# DIO.net
KiCad netlist of a schematic drawn in Altium Designer
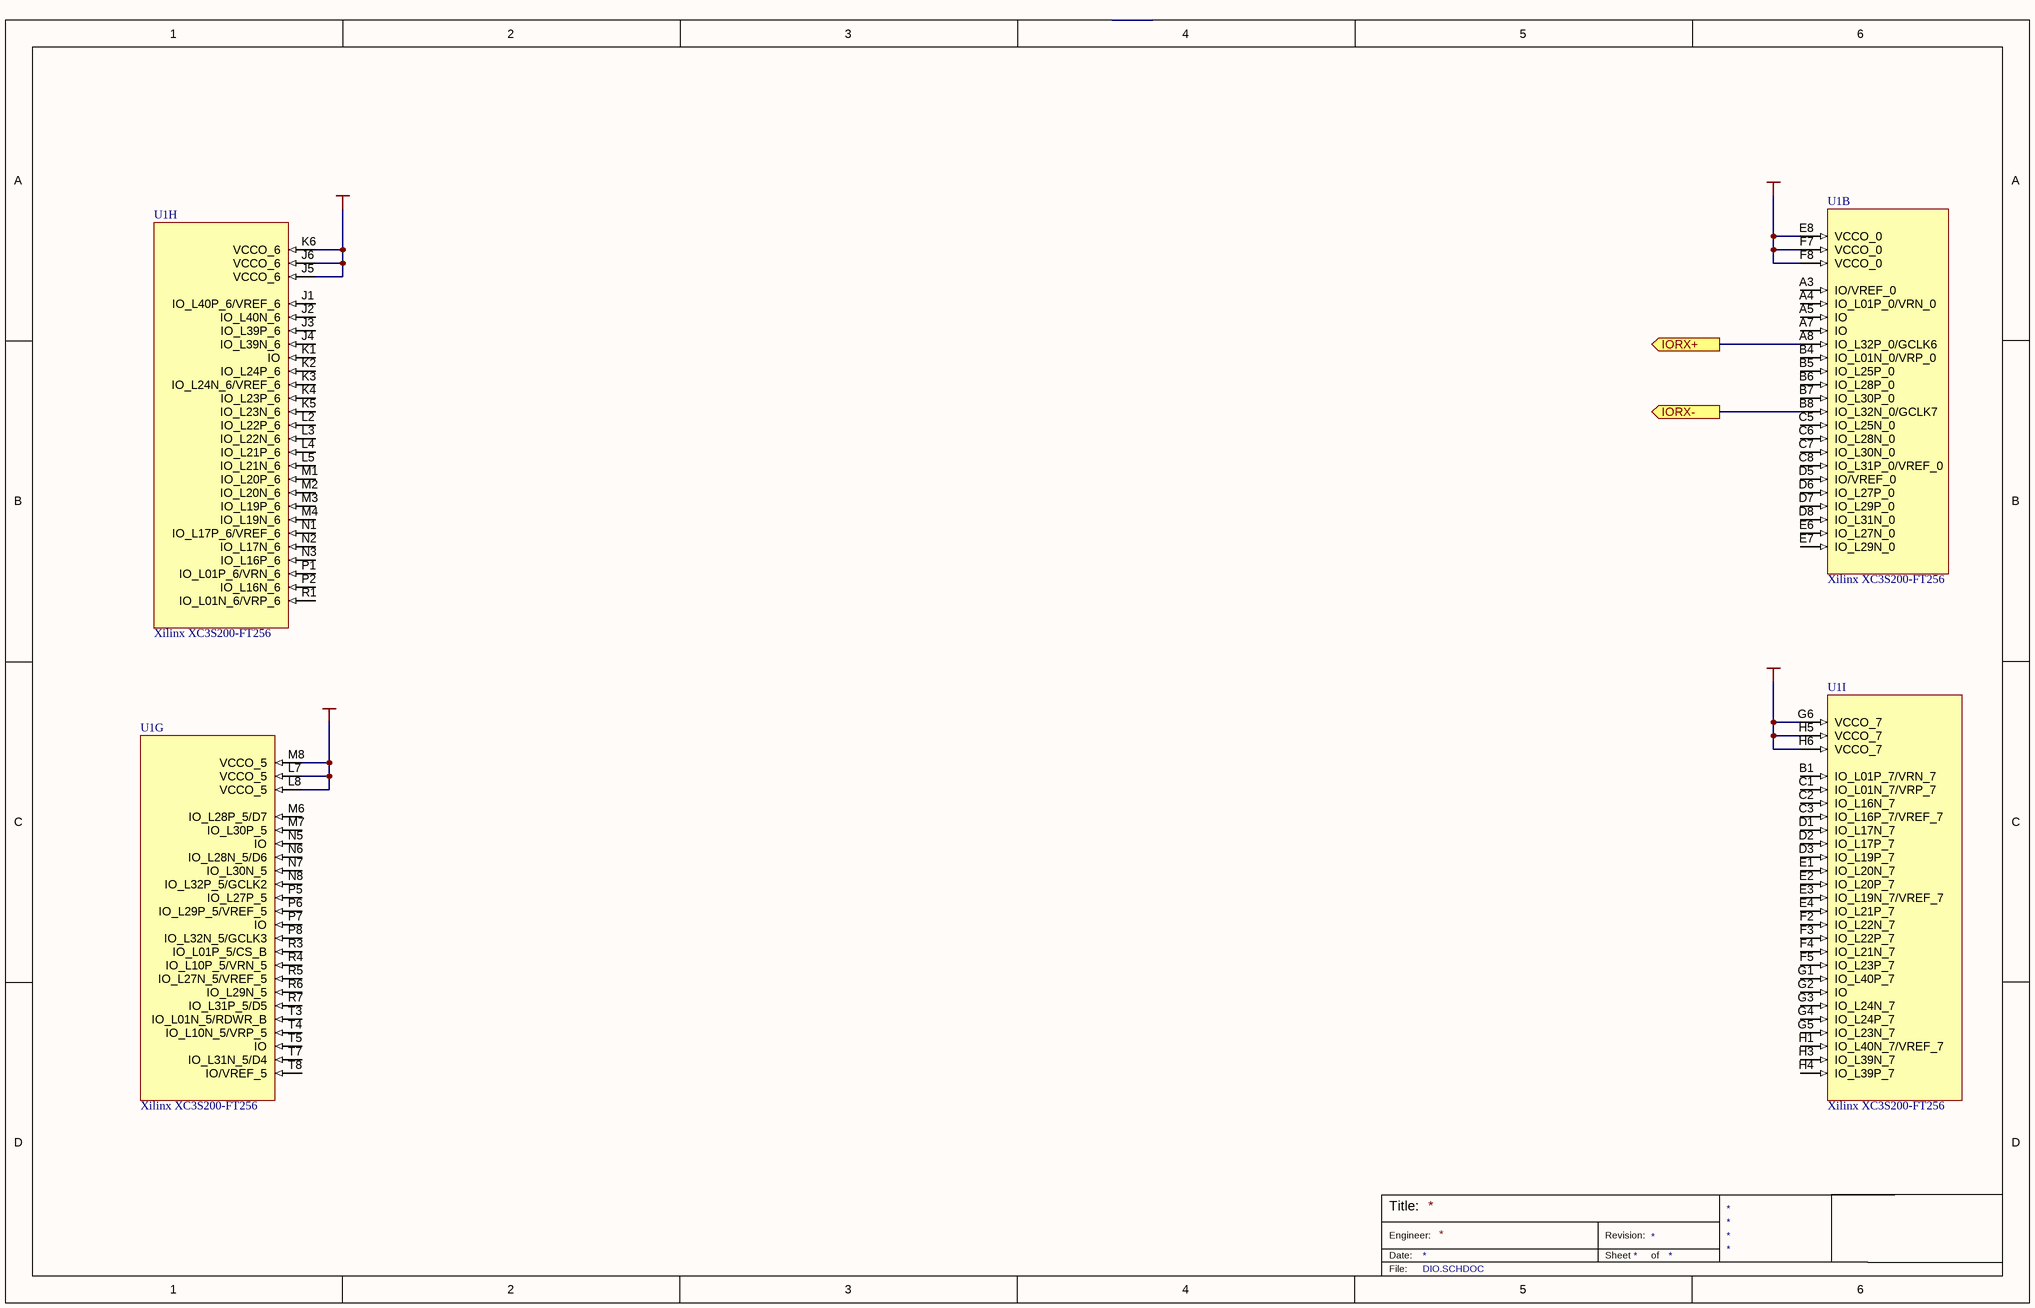
[diagram p0: DIO.SCHDOC]

(export (version "E")
  (design (tool "Eeschema 10.0.6"))
  (components
    (comp (ref "U1")
      (value "Xilinx XC3S200-FT256")
      (footprint "Xilinx FT256 BGA")
      (description "Xilinx Spartan-3 FPGA")
      (libsource (lib "") (part "XC3S200-FT256_1"))
    )
  )
  (nets
    (net (code "1") (name "+2.5VCC") (class "Default")
      (node (ref "U1") (pin "E8") (pinfunction "VCCO_0_E8") (pintype "input"))
      (node (ref "U1") (pin "F7") (pinfunction "VCCO_0_F7") (pintype "input"))
      (node (ref "U1") (pin "F8") (pinfunction "VCCO_0_F8") (pintype "input"))
      (node (ref "U1") (pin "G6") (pinfunction "VCCO_7_G6") (pintype "input"))
      (node (ref "U1") (pin "H5") (pinfunction "VCCO_7_H5") (pintype "input"))
      (node (ref "U1") (pin "H6") (pinfunction "VCCO_7_H6") (pintype "input"))
      (node (ref "U1") (pin "J5") (pinfunction "VCCO_6_J5") (pintype "input"))
      (node (ref "U1") (pin "J6") (pinfunction "VCCO_6_J6") (pintype "input"))
      (node (ref "U1") (pin "K6") (pinfunction "VCCO_6_K6") (pintype "input"))
      (node (ref "U1") (pin "L7") (pinfunction "VCCO_5_L7") (pintype "input"))
      (node (ref "U1") (pin "L8") (pinfunction "VCCO_5_L8") (pintype "input"))
      (node (ref "U1") (pin "M8") (pinfunction "VCCO_5_M8") (pintype "input"))
    )
    (net (code "2") (name "/IORX+") (class "Default")
      (node (ref "U1") (pin "A8") (pinfunction "IO_L32P_0/GCLK6_A8") (pintype "input"))
    )
    (net (code "3") (name "/IORX-") (class "Default")
      (node (ref "U1") (pin "B8") (pinfunction "IO_L32N_0/GCLK7_B8") (pintype "input"))
    )
    (net (code "4") (name "unconnected-(U1B-IO-PadA5)") (class "Default")
      (node (ref "U1") (pin "A5") (pinfunction "IO_A5") (pintype "input"))
    )
    (net (code "5") (name "unconnected-(U1B-IO-PadA7)") (class "Default")
      (node (ref "U1") (pin "A7") (pinfunction "IO_A7") (pintype "input"))
    )
    (net (code "6") (name "unconnected-(U1B-IO_L01N_0{slash}VRP_0-PadB4)") (class "Default")
      (node (ref "U1") (pin "B4") (pinfunction "IO_L01N_0/VRP_0_B4") (pintype "input"))
    )
    (net (code "7") (name "unconnected-(U1B-IO_L01P_0{slash}VRN_0-PadA4)") (class "Default")
      (node (ref "U1") (pin "A4") (pinfunction "IO_L01P_0/VRN_0_A4") (pintype "input"))
    )
    (net (code "8") (name "unconnected-(U1B-IO_L25N_0-PadC5)") (class "Default")
      (node (ref "U1") (pin "C5") (pinfunction "IO_L25N_0_C5") (pintype "input"))
    )
    (net (code "9") (name "unconnected-(U1B-IO_L25P_0-PadB5)") (class "Default")
      (node (ref "U1") (pin "B5") (pinfunction "IO_L25P_0_B5") (pintype "input"))
    )
    (net (code "10") (name "unconnected-(U1B-IO_L27N_0-PadE6)") (class "Default")
      (node (ref "U1") (pin "E6") (pinfunction "IO_L27N_0_E6") (pintype "input"))
    )
    (net (code "11") (name "unconnected-(U1B-IO_L27P_0-PadD6)") (class "Default")
      (node (ref "U1") (pin "D6") (pinfunction "IO_L27P_0_D6") (pintype "input"))
    )
    (net (code "12") (name "unconnected-(U1B-IO_L28N_0-PadC6)") (class "Default")
      (node (ref "U1") (pin "C6") (pinfunction "IO_L28N_0_C6") (pintype "input"))
    )
    (net (code "13") (name "unconnected-(U1B-IO_L28P_0-PadB6)") (class "Default")
      (node (ref "U1") (pin "B6") (pinfunction "IO_L28P_0_B6") (pintype "input"))
    )
    (net (code "14") (name "unconnected-(U1B-IO_L29N_0-PadE7)") (class "Default")
      (node (ref "U1") (pin "E7") (pinfunction "IO_L29N_0_E7") (pintype "input"))
    )
    (net (code "15") (name "unconnected-(U1B-IO_L29P_0-PadD7)") (class "Default")
      (node (ref "U1") (pin "D7") (pinfunction "IO_L29P_0_D7") (pintype "input"))
    )
    (net (code "16") (name "unconnected-(U1B-IO_L30N_0-PadC7)") (class "Default")
      (node (ref "U1") (pin "C7") (pinfunction "IO_L30N_0_C7") (pintype "input"))
    )
    (net (code "17") (name "unconnected-(U1B-IO_L30P_0-PadB7)") (class "Default")
      (node (ref "U1") (pin "B7") (pinfunction "IO_L30P_0_B7") (pintype "input"))
    )
    (net (code "18") (name "unconnected-(U1B-IO_L31N_0-PadD8)") (class "Default")
      (node (ref "U1") (pin "D8") (pinfunction "IO_L31N_0_D8") (pintype "input"))
    )
    (net (code "19") (name "unconnected-(U1B-IO_L31P_0{slash}VREF_0-PadC8)") (class "Default")
      (node (ref "U1") (pin "C8") (pinfunction "IO_L31P_0/VREF_0_C8") (pintype "input"))
    )
    (net (code "20") (name "unconnected-(U1B-IO{slash}VREF_0-PadA3)") (class "Default")
      (node (ref "U1") (pin "A3") (pinfunction "IO/VREF_0_A3") (pintype "input"))
    )
    (net (code "21") (name "unconnected-(U1B-IO{slash}VREF_0-PadD5)") (class "Default")
      (node (ref "U1") (pin "D5") (pinfunction "IO/VREF_0_D5") (pintype "input"))
    )
    (net (code "22") (name "unconnected-(U1G-IO-PadN5)") (class "Default")
      (node (ref "U1") (pin "N5") (pinfunction "IO_N5") (pintype "input"))
    )
    (net (code "23") (name "unconnected-(U1G-IO-PadP7)") (class "Default")
      (node (ref "U1") (pin "P7") (pinfunction "IO_P7") (pintype "input"))
    )
    (net (code "24") (name "unconnected-(U1G-IO-PadT5)") (class "Default")
      (node (ref "U1") (pin "T5") (pinfunction "IO_T5") (pintype "input"))
    )
    (net (code "25") (name "unconnected-(U1G-IO_L01N_5{slash}RDWR_B-PadT3)") (class "Default")
      (node (ref "U1") (pin "T3") (pinfunction "IO_L01N_5/RDWR_B_T3") (pintype "input"))
    )
    (net (code "26") (name "unconnected-(U1G-IO_L01P_5{slash}CS_B-PadR3)") (class "Default")
      (node (ref "U1") (pin "R3") (pinfunction "IO_L01P_5/CS_B_R3") (pintype "input"))
    )
    (net (code "27") (name "unconnected-(U1G-IO_L10N_5{slash}VRP_5-PadT4)") (class "Default")
      (node (ref "U1") (pin "T4") (pinfunction "IO_L10N_5/VRP_5_T4") (pintype "input"))
    )
    (net (code "28") (name "unconnected-(U1G-IO_L10P_5{slash}VRN_5-PadR4)") (class "Default")
      (node (ref "U1") (pin "R4") (pinfunction "IO_L10P_5/VRN_5_R4") (pintype "input"))
    )
    (net (code "29") (name "unconnected-(U1G-IO_L27N_5{slash}VREF_5-PadR5)") (class "Default")
      (node (ref "U1") (pin "R5") (pinfunction "IO_L27N_5/VREF_5_R5") (pintype "input"))
    )
    (net (code "30") (name "unconnected-(U1G-IO_L27P_5-PadP5)") (class "Default")
      (node (ref "U1") (pin "P5") (pinfunction "IO_L27P_5_P5") (pintype "input"))
    )
    (net (code "31") (name "unconnected-(U1G-IO_L28N_5{slash}D6-PadN6)") (class "Default")
      (node (ref "U1") (pin "N6") (pinfunction "IO_L28N_5/D6_N6") (pintype "input"))
    )
    (net (code "32") (name "unconnected-(U1G-IO_L28P_5{slash}D7-PadM6)") (class "Default")
      (node (ref "U1") (pin "M6") (pinfunction "IO_L28P_5/D7_M6") (pintype "input"))
    )
    (net (code "33") (name "unconnected-(U1G-IO_L29N_5-PadR6)") (class "Default")
      (node (ref "U1") (pin "R6") (pinfunction "IO_L29N_5_R6") (pintype "input"))
    )
    (net (code "34") (name "unconnected-(U1G-IO_L29P_5{slash}VREF_5-PadP6)") (class "Default")
      (node (ref "U1") (pin "P6") (pinfunction "IO_L29P_5/VREF_5_P6") (pintype "input"))
    )
    (net (code "35") (name "unconnected-(U1G-IO_L30N_5-PadN7)") (class "Default")
      (node (ref "U1") (pin "N7") (pinfunction "IO_L30N_5_N7") (pintype "input"))
    )
    (net (code "36") (name "unconnected-(U1G-IO_L30P_5-PadM7)") (class "Default")
      (node (ref "U1") (pin "M7") (pinfunction "IO_L30P_5_M7") (pintype "input"))
    )
    (net (code "37") (name "unconnected-(U1G-IO_L31N_5{slash}D4-PadT7)") (class "Default")
      (node (ref "U1") (pin "T7") (pinfunction "IO_L31N_5/D4_T7") (pintype "input"))
    )
    (net (code "38") (name "unconnected-(U1G-IO_L31P_5{slash}D5-PadR7)") (class "Default")
      (node (ref "U1") (pin "R7") (pinfunction "IO_L31P_5/D5_R7") (pintype "input"))
    )
    (net (code "39") (name "unconnected-(U1G-IO_L32N_5{slash}GCLK3-PadP8)") (class "Default")
      (node (ref "U1") (pin "P8") (pinfunction "IO_L32N_5/GCLK3_P8") (pintype "input"))
    )
    (net (code "40") (name "unconnected-(U1G-IO_L32P_5{slash}GCLK2-PadN8)") (class "Default")
      (node (ref "U1") (pin "N8") (pinfunction "IO_L32P_5/GCLK2_N8") (pintype "input"))
    )
    (net (code "41") (name "unconnected-(U1G-IO{slash}VREF_5-PadT8)") (class "Default")
      (node (ref "U1") (pin "T8") (pinfunction "IO/VREF_5_T8") (pintype "input"))
    )
    (net (code "42") (name "unconnected-(U1H-IO-PadK1)") (class "Default")
      (node (ref "U1") (pin "K1") (pinfunction "IO_K1") (pintype "input"))
    )
    (net (code "43") (name "unconnected-(U1H-IO_L01N_6{slash}VRP_6-PadR1)") (class "Default")
      (node (ref "U1") (pin "R1") (pinfunction "IO_L01N_6/VRP_6_R1") (pintype "input"))
    )
    (net (code "44") (name "unconnected-(U1H-IO_L01P_6{slash}VRN_6-PadP1)") (class "Default")
      (node (ref "U1") (pin "P1") (pinfunction "IO_L01P_6/VRN_6_P1") (pintype "input"))
    )
    (net (code "45") (name "unconnected-(U1H-IO_L16N_6-PadP2)") (class "Default")
      (node (ref "U1") (pin "P2") (pinfunction "IO_L16N_6_P2") (pintype "input"))
    )
    (net (code "46") (name "unconnected-(U1H-IO_L16P_6-PadN3)") (class "Default")
      (node (ref "U1") (pin "N3") (pinfunction "IO_L16P_6_N3") (pintype "input"))
    )
    (net (code "47") (name "unconnected-(U1H-IO_L17N_6-PadN2)") (class "Default")
      (node (ref "U1") (pin "N2") (pinfunction "IO_L17N_6_N2") (pintype "input"))
    )
    (net (code "48") (name "unconnected-(U1H-IO_L17P_6{slash}VREF_6-PadN1)") (class "Default")
      (node (ref "U1") (pin "N1") (pinfunction "IO_L17P_6/VREF_6_N1") (pintype "input"))
    )
    (net (code "49") (name "unconnected-(U1H-IO_L19N_6-PadM4)") (class "Default")
      (node (ref "U1") (pin "M4") (pinfunction "IO_L19N_6_M4") (pintype "input"))
    )
    (net (code "50") (name "unconnected-(U1H-IO_L19P_6-PadM3)") (class "Default")
      (node (ref "U1") (pin "M3") (pinfunction "IO_L19P_6_M3") (pintype "input"))
    )
    (net (code "51") (name "unconnected-(U1H-IO_L20N_6-PadM2)") (class "Default")
      (node (ref "U1") (pin "M2") (pinfunction "IO_L20N_6_M2") (pintype "input"))
    )
    (net (code "52") (name "unconnected-(U1H-IO_L20P_6-PadM1)") (class "Default")
      (node (ref "U1") (pin "M1") (pinfunction "IO_L20P_6_M1") (pintype "input"))
    )
    (net (code "53") (name "unconnected-(U1H-IO_L21N_6-PadL5)") (class "Default")
      (node (ref "U1") (pin "L5") (pinfunction "IO_L21N_6_L5") (pintype "input"))
    )
    (net (code "54") (name "unconnected-(U1H-IO_L21P_6-PadL4)") (class "Default")
      (node (ref "U1") (pin "L4") (pinfunction "IO_L21P_6_L4") (pintype "input"))
    )
    (net (code "55") (name "unconnected-(U1H-IO_L22N_6-PadL3)") (class "Default")
      (node (ref "U1") (pin "L3") (pinfunction "IO_L22N_6_L3") (pintype "input"))
    )
    (net (code "56") (name "unconnected-(U1H-IO_L22P_6-PadL2)") (class "Default")
      (node (ref "U1") (pin "L2") (pinfunction "IO_L22P_6_L2") (pintype "input"))
    )
    (net (code "57") (name "unconnected-(U1H-IO_L23N_6-PadK5)") (class "Default")
      (node (ref "U1") (pin "K5") (pinfunction "IO_L23N_6_K5") (pintype "input"))
    )
    (net (code "58") (name "unconnected-(U1H-IO_L23P_6-PadK4)") (class "Default")
      (node (ref "U1") (pin "K4") (pinfunction "IO_L23P_6_K4") (pintype "input"))
    )
    (net (code "59") (name "unconnected-(U1H-IO_L24N_6{slash}VREF_6-PadK3)") (class "Default")
      (node (ref "U1") (pin "K3") (pinfunction "IO_L24N_6/VREF_6_K3") (pintype "input"))
    )
    (net (code "60") (name "unconnected-(U1H-IO_L24P_6-PadK2)") (class "Default")
      (node (ref "U1") (pin "K2") (pinfunction "IO_L24P_6_K2") (pintype "input"))
    )
    (net (code "61") (name "unconnected-(U1H-IO_L39N_6-PadJ4)") (class "Default")
      (node (ref "U1") (pin "J4") (pinfunction "IO_L39N_6_J4") (pintype "input"))
    )
    (net (code "62") (name "unconnected-(U1H-IO_L39P_6-PadJ3)") (class "Default")
      (node (ref "U1") (pin "J3") (pinfunction "IO_L39P_6_J3") (pintype "input"))
    )
    (net (code "63") (name "unconnected-(U1H-IO_L40N_6-PadJ2)") (class "Default")
      (node (ref "U1") (pin "J2") (pinfunction "IO_L40N_6_J2") (pintype "input"))
    )
    (net (code "64") (name "unconnected-(U1H-IO_L40P_6{slash}VREF_6-PadJ1)") (class "Default")
      (node (ref "U1") (pin "J1") (pinfunction "IO_L40P_6/VREF_6_J1") (pintype "input"))
    )
    (net (code "65") (name "unconnected-(U1I-IO-PadG2)") (class "Default")
      (node (ref "U1") (pin "G2") (pinfunction "IO_G2") (pintype "input"))
    )
    (net (code "66") (name "unconnected-(U1I-IO_L01N_7{slash}VRP_7-PadC1)") (class "Default")
      (node (ref "U1") (pin "C1") (pinfunction "IO_L01N_7/VRP_7_C1") (pintype "input"))
    )
    (net (code "67") (name "unconnected-(U1I-IO_L01P_7{slash}VRN_7-PadB1)") (class "Default")
      (node (ref "U1") (pin "B1") (pinfunction "IO_L01P_7/VRN_7_B1") (pintype "input"))
    )
    (net (code "68") (name "unconnected-(U1I-IO_L16N_7-PadC2)") (class "Default")
      (node (ref "U1") (pin "C2") (pinfunction "IO_L16N_7_C2") (pintype "input"))
    )
    (net (code "69") (name "unconnected-(U1I-IO_L16P_7{slash}VREF_7-PadC3)") (class "Default")
      (node (ref "U1") (pin "C3") (pinfunction "IO_L16P_7/VREF_7_C3") (pintype "input"))
    )
    (net (code "70") (name "unconnected-(U1I-IO_L17N_7-PadD1)") (class "Default")
      (node (ref "U1") (pin "D1") (pinfunction "IO_L17N_7_D1") (pintype "input"))
    )
    (net (code "71") (name "unconnected-(U1I-IO_L17P_7-PadD2)") (class "Default")
      (node (ref "U1") (pin "D2") (pinfunction "IO_L17P_7_D2") (pintype "input"))
    )
    (net (code "72") (name "unconnected-(U1I-IO_L19N_7{slash}VREF_7-PadE3)") (class "Default")
      (node (ref "U1") (pin "E3") (pinfunction "IO_L19N_7/VREF_7_E3") (pintype "input"))
    )
    (net (code "73") (name "unconnected-(U1I-IO_L19P_7-PadD3)") (class "Default")
      (node (ref "U1") (pin "D3") (pinfunction "IO_L19P_7_D3") (pintype "input"))
    )
    (net (code "74") (name "unconnected-(U1I-IO_L20N_7-PadE1)") (class "Default")
      (node (ref "U1") (pin "E1") (pinfunction "IO_L20N_7_E1") (pintype "input"))
    )
    (net (code "75") (name "unconnected-(U1I-IO_L20P_7-PadE2)") (class "Default")
      (node (ref "U1") (pin "E2") (pinfunction "IO_L20P_7_E2") (pintype "input"))
    )
    (net (code "76") (name "unconnected-(U1I-IO_L21N_7-PadF4)") (class "Default")
      (node (ref "U1") (pin "F4") (pinfunction "IO_L21N_7_F4") (pintype "input"))
    )
    (net (code "77") (name "unconnected-(U1I-IO_L21P_7-PadE4)") (class "Default")
      (node (ref "U1") (pin "E4") (pinfunction "IO_L21P_7_E4") (pintype "input"))
    )
    (net (code "78") (name "unconnected-(U1I-IO_L22N_7-PadF2)") (class "Default")
      (node (ref "U1") (pin "F2") (pinfunction "IO_L22N_7_F2") (pintype "input"))
    )
    (net (code "79") (name "unconnected-(U1I-IO_L22P_7-PadF3)") (class "Default")
      (node (ref "U1") (pin "F3") (pinfunction "IO_L22P_7_F3") (pintype "input"))
    )
    (net (code "80") (name "unconnected-(U1I-IO_L23N_7-PadG5)") (class "Default")
      (node (ref "U1") (pin "G5") (pinfunction "IO_L23N_7_G5") (pintype "input"))
    )
    (net (code "81") (name "unconnected-(U1I-IO_L23P_7-PadF5)") (class "Default")
      (node (ref "U1") (pin "F5") (pinfunction "IO_L23P_7_F5") (pintype "input"))
    )
    (net (code "82") (name "unconnected-(U1I-IO_L24N_7-PadG3)") (class "Default")
      (node (ref "U1") (pin "G3") (pinfunction "IO_L24N_7_G3") (pintype "input"))
    )
    (net (code "83") (name "unconnected-(U1I-IO_L24P_7-PadG4)") (class "Default")
      (node (ref "U1") (pin "G4") (pinfunction "IO_L24P_7_G4") (pintype "input"))
    )
    (net (code "84") (name "unconnected-(U1I-IO_L39N_7-PadH3)") (class "Default")
      (node (ref "U1") (pin "H3") (pinfunction "IO_L39N_7_H3") (pintype "input"))
    )
    (net (code "85") (name "unconnected-(U1I-IO_L39P_7-PadH4)") (class "Default")
      (node (ref "U1") (pin "H4") (pinfunction "IO_L39P_7_H4") (pintype "input"))
    )
    (net (code "86") (name "unconnected-(U1I-IO_L40N_7{slash}VREF_7-PadH1)") (class "Default")
      (node (ref "U1") (pin "H1") (pinfunction "IO_L40N_7/VREF_7_H1") (pintype "input"))
    )
    (net (code "87") (name "unconnected-(U1I-IO_L40P_7-PadG1)") (class "Default")
      (node (ref "U1") (pin "G1") (pinfunction "IO_L40P_7_G1") (pintype "input"))
    )
  )
)
